# Sheet1.net
KiCad netlist of a schematic drawn in Altium Designer
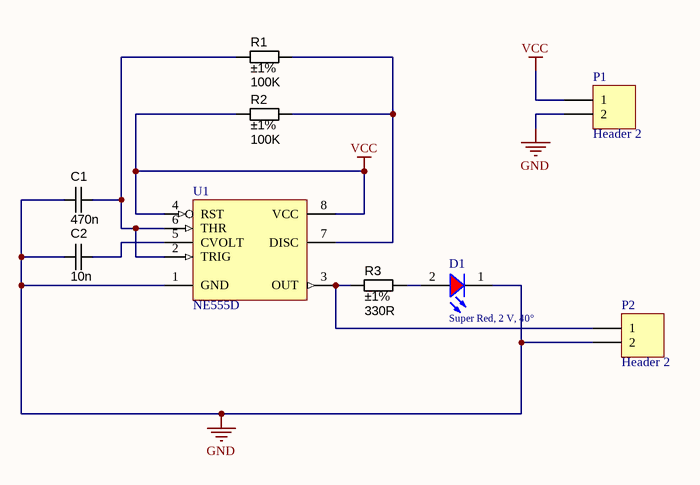
[diagram p0: Sheet1.SchDoc]

(export (version "E")
  (design (tool "Eeschema 10.0.6"))
  (components
    (comp (ref "C1")
      (value "470n")
      (footprint "CAPC2012X135N")
      (description "Capacitor SMD Cer 10uF 10% 10V X5R 0805")
      (fields (field (name "TOLERANCE") "±10%") (field (name "Comment") "approved sub OK"))
      (libsource (lib "PBL - Capacitors") (part "CAPC_10u_0805_10V"))
    )
    (comp (ref "C2")
      (value "10n")
      (footprint "CAPC2012X135N")
      (description "Capacitor SMD Cer 10uF 10% 10V X5R 0805")
      (fields (field (name "TOLERANCE") "±10%") (field (name "Comment") "approved sub OK"))
      (libsource (lib "PBL - Capacitors") (part "CAPC_10u_0805_10V"))
    )
    (comp (ref "D1")
      (value "Super Red, 2 V, 40°")
      (footprint "WL-TMRC_3 mm_without stopper")
      (description "WL-TMRC THT Mono-color Round Color, 3 mm, without stopper, Super Red, 40°, 2 V")
      (fields (field (name "PART NUMBER") "151031SS04000") (field (name "PUBLISHER") "Wurth Elektronik"))
      (libsource (lib "ALTIUM-WL-LED-rev18a") (part "151031SS04000"))
    )
    (comp (ref "P1")
      (value "Header 2")
      (footprint "HDR1X2")
      (description "Header, 2-Pin")
      (fields (field (name "PUBLISHER") "Altium Limited"))
      (libsource (lib "Miscellaneous Connectors") (part "Header 2"))
    )
    (comp (ref "P2")
      (value "Header 2")
      (footprint "HDR1X2")
      (description "Header, 2-Pin")
      (fields (field (name "PUBLISHER") "Altium Limited"))
      (libsource (lib "Miscellaneous Connectors") (part "Header 2"))
    )
    (comp (ref "R1")
      (value "100K")
      (footprint "RESC2012X70N")
      (description "Resistor SMD chip 10k Ohm 0.125W 1% 0805")
      (fields (field (name "TOLERANCE") "±1%") (field (name "Comment") "Thick Film"))
      (libsource (lib "PBL - Resistors") (part "RES_10K_0805_1%"))
    )
    (comp (ref "R2")
      (value "100K")
      (footprint "RESC2012X70N")
      (description "Resistor SMD chip 1k Ohm 0.125W 1% 0805")
      (fields (field (name "TOLERANCE") "±1%") (field (name "Comment") "Thick Film"))
      (libsource (lib "PBL - Resistors") (part "RES_1K_0805_1%"))
    )
    (comp (ref "R3")
      (value "330R")
      (footprint "RESC2012X70N")
      (description "Resistor SMD chip 1k Ohm 0.125W 1% 0805")
      (fields (field (name "TOLERANCE") "±1%") (field (name "Comment") "Thick Film"))
      (libsource (lib "PBL - Resistors") (part "RES_1K_0805_1%"))
    )
    (comp (ref "U1")
      (value "NE555D")
      (footprint "D008_N")
      (description "Precision Timer")
      (fields (field (name "PUBLISHER") "Altium Limited"))
      (libsource (lib "TI Analog Timer Circuit") (part "NE555D"))
    )
  )
  (nets
    (net (code "1") (name "GND") (class "Default")
      (node (ref "C1") (pin "1") (pintype "passive"))
      (node (ref "C2") (pin "1") (pintype "passive"))
      (node (ref "D1") (pin "1") (pinfunction "K_1") (pintype "passive"))
      (node (ref "P1") (pin "2") (pinfunction "2_2") (pintype "passive"))
      (node (ref "P2") (pin "2") (pinfunction "2_2") (pintype "passive"))
      (node (ref "U1") (pin "1") (pinfunction "GND_1") (pintype "power_in"))
    )
    (net (code "2") (name "Net-(D1-A)") (class "Default")
      (node (ref "D1") (pin "2") (pinfunction "A_2") (pintype "passive"))
      (node (ref "R3") (pin "2") (pinfunction "2_2") (pintype "passive"))
    )
    (net (code "3") (name "Net-(U1-CVOLT)") (class "Default")
      (node (ref "C2") (pin "2") (pintype "passive"))
      (node (ref "U1") (pin "5") (pinfunction "CVOLT_5") (pintype "passive"))
    )
    (net (code "4") (name "Net-(U1-DISC)") (class "Default")
      (node (ref "R1") (pin "2") (pinfunction "2_2") (pintype "passive"))
      (node (ref "R2") (pin "2") (pinfunction "2_2") (pintype "passive"))
      (node (ref "U1") (pin "7") (pinfunction "DISC_7") (pintype "open_collector"))
    )
    (net (code "5") (name "Net-(U1-OUT)") (class "Default")
      (node (ref "P2") (pin "1") (pinfunction "1_1") (pintype "passive"))
      (node (ref "R3") (pin "1") (pinfunction "1_1") (pintype "passive"))
      (node (ref "U1") (pin "3") (pinfunction "OUT_3") (pintype "output"))
    )
    (net (code "6") (name "Net-(U1-THR)") (class "Default")
      (node (ref "C1") (pin "2") (pintype "passive"))
      (node (ref "R1") (pin "1") (pinfunction "1_1") (pintype "passive"))
      (node (ref "U1") (pin "2") (pinfunction "TRIG_2") (pintype "input"))
      (node (ref "U1") (pin "6") (pinfunction "THR_6") (pintype "input"))
    )
    (net (code "7") (name "VCC") (class "Default")
      (node (ref "P1") (pin "1") (pinfunction "1_1") (pintype "passive"))
      (node (ref "R2") (pin "1") (pinfunction "1_1") (pintype "passive"))
      (node (ref "U1") (pin "4") (pinfunction "RST_4") (pintype "input"))
      (node (ref "U1") (pin "8") (pinfunction "VCC_8") (pintype "power_in"))
    )
  )
)
